# hero_board.net
KiCad netlist of a schematic drawn in EAGLE
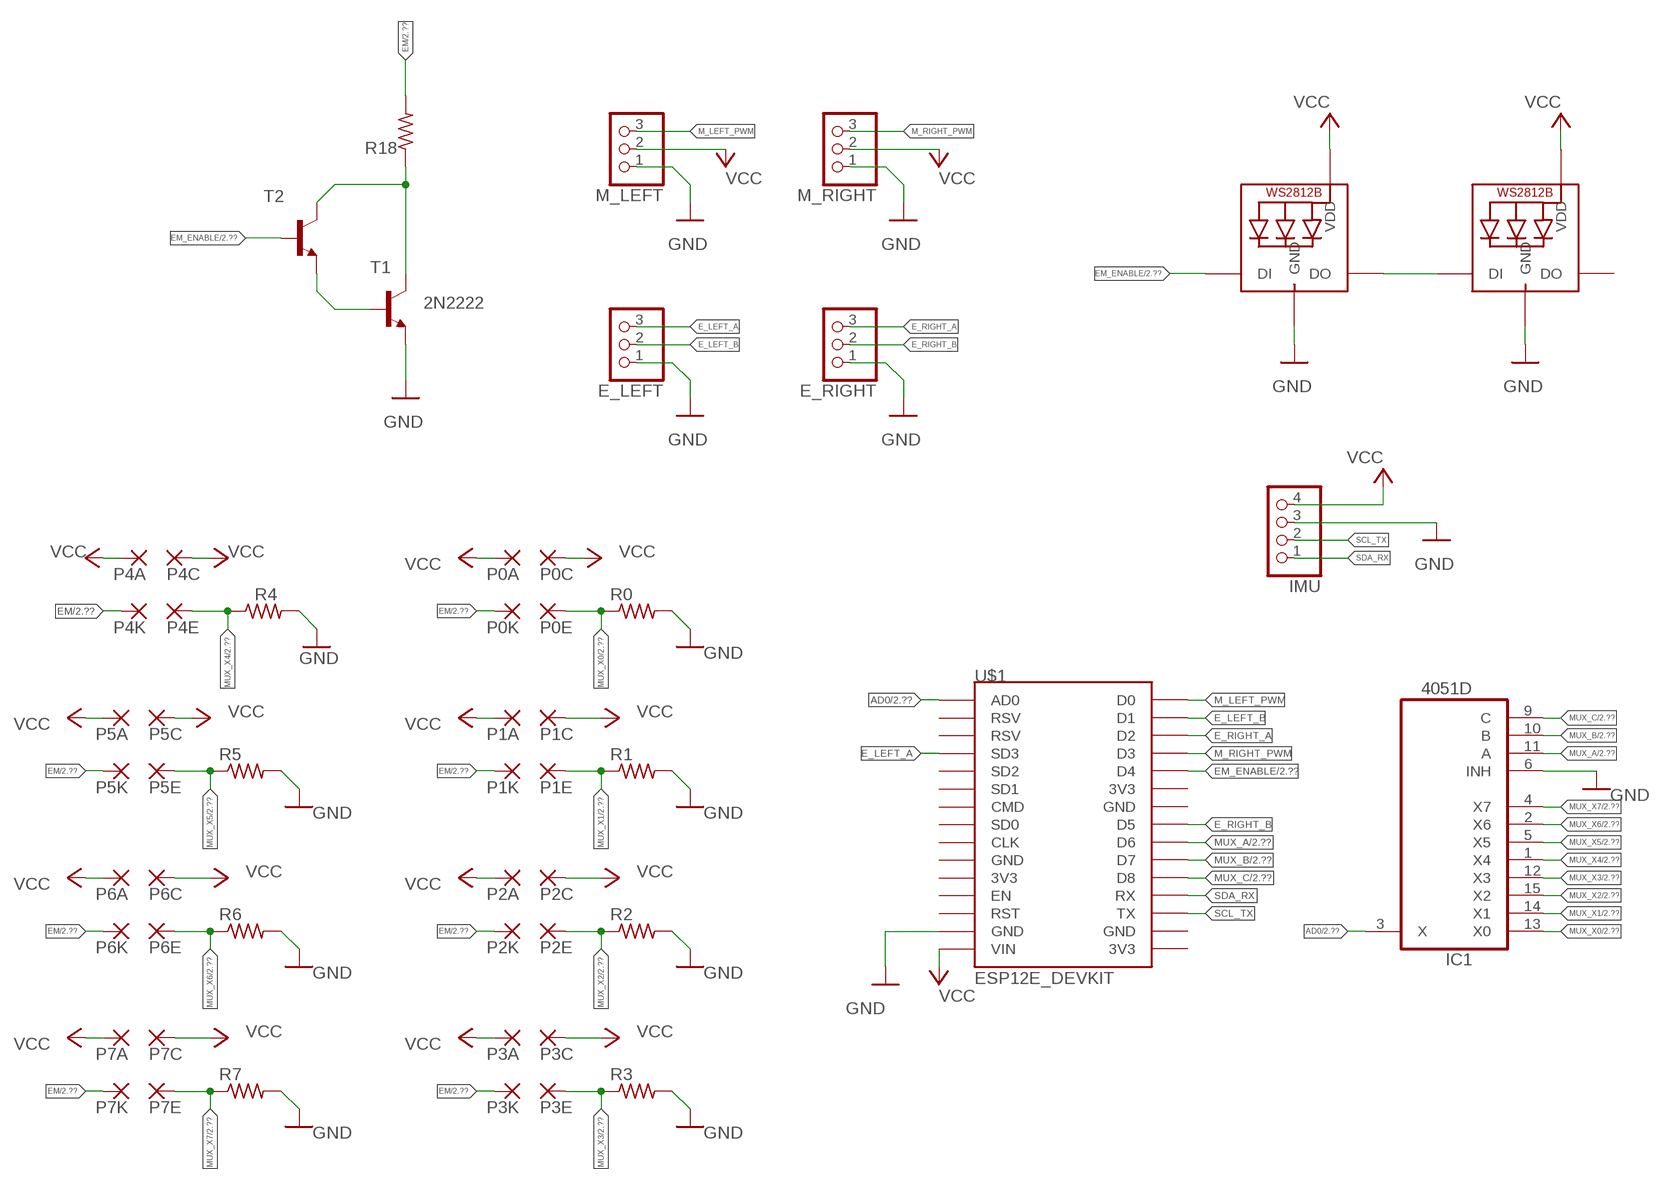
[diagram p0: schematic, sheet 1]
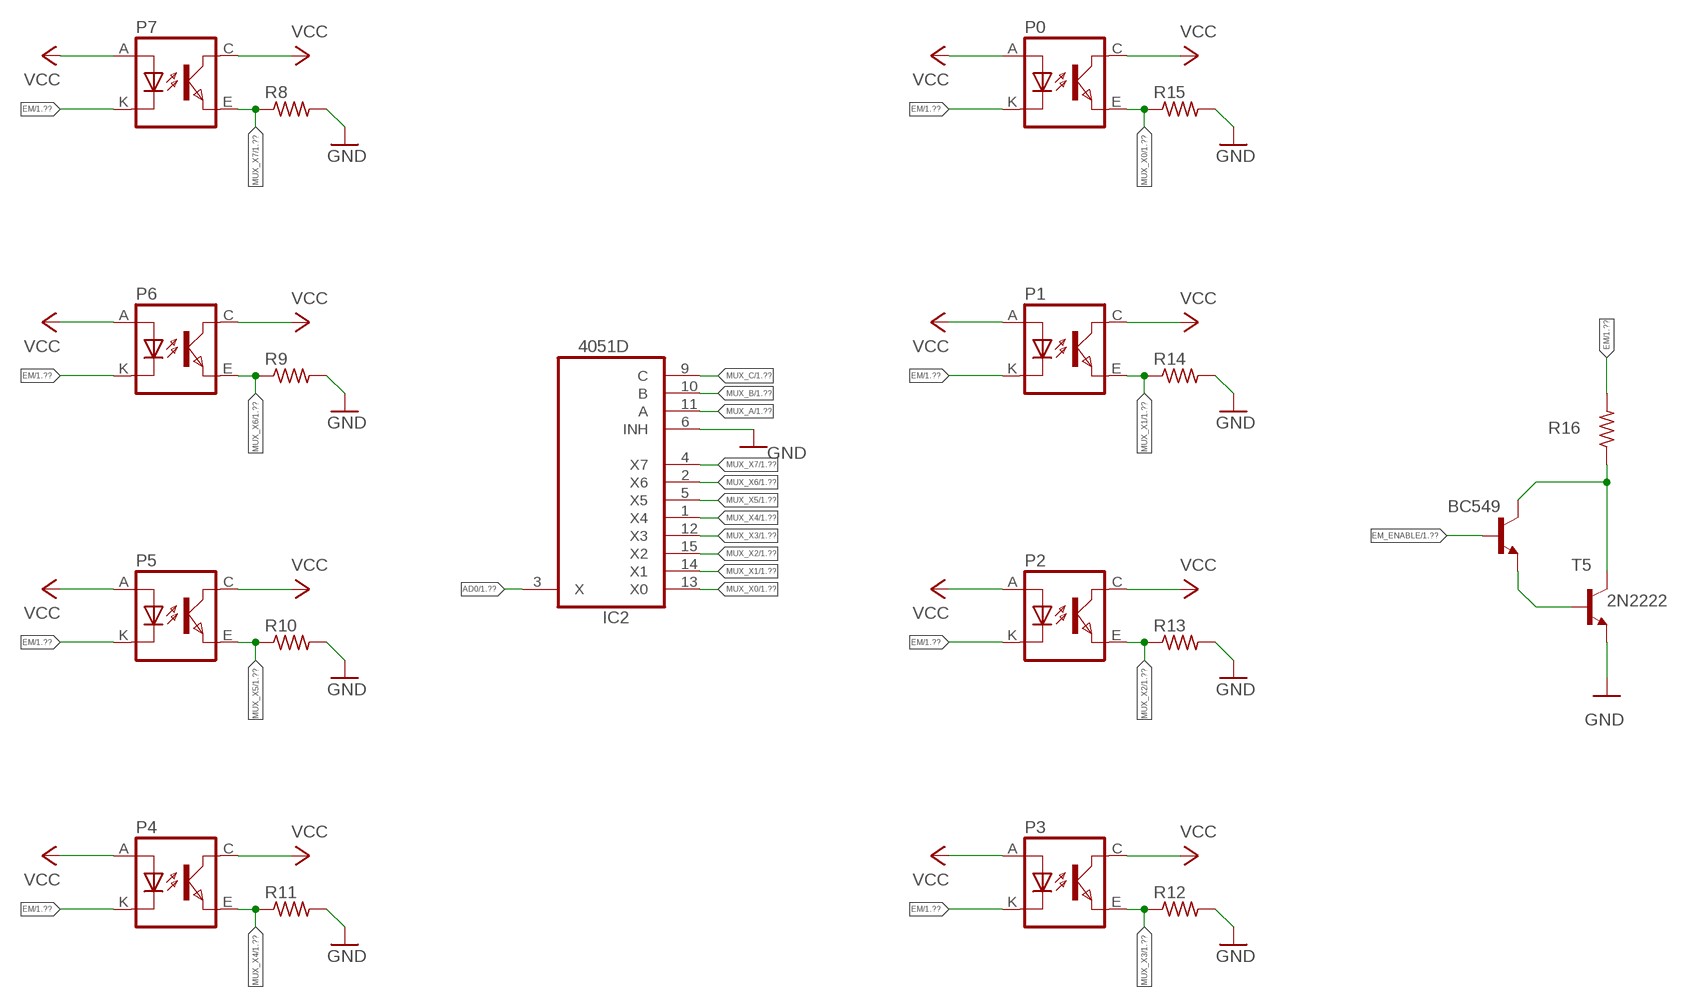
[diagram p1: schematic, sheet 2]

(export (version "E")
  (design (tool "Eeschema 10.0.6"))
  (components
    (comp (ref "BC549")
      (value "BC549-NPN-TO92-CBE")
      (footprint "eagle-import:TO92-CBE")
      (fields (field (name "SPICEPREFIX") "J"))
      (libsource (lib "eagle-import") (part "-NPN-TO92-CBEBC549"))
    )
    (comp (ref "IC2")
      (value "4051D")
      (footprint "eagle-import:SO16")
      (libsource (lib "eagle-import") (part "4051D"))
    )
    (comp (ref "P0")
      (value "TCRT5000")
      (footprint "eagle-import:TCRT5000")
      (libsource (lib "eagle-import") (part "TCRT5000"))
    )
    (comp (ref "P1")
      (value "TCRT5000")
      (footprint "eagle-import:TCRT5000")
      (libsource (lib "eagle-import") (part "TCRT5000"))
    )
    (comp (ref "P2")
      (value "TCRT5000")
      (footprint "eagle-import:TCRT5000")
      (libsource (lib "eagle-import") (part "TCRT5000"))
    )
    (comp (ref "P3")
      (value "TCRT5000")
      (footprint "eagle-import:TCRT5000")
      (libsource (lib "eagle-import") (part "TCRT5000"))
    )
    (comp (ref "P4")
      (value "TCRT5000")
      (footprint "eagle-import:TCRT5000")
      (libsource (lib "eagle-import") (part "TCRT5000"))
    )
    (comp (ref "P5")
      (value "TCRT5000")
      (footprint "eagle-import:TCRT5000")
      (libsource (lib "eagle-import") (part "TCRT5000"))
    )
    (comp (ref "P6")
      (value "TCRT5000")
      (footprint "eagle-import:TCRT5000")
      (libsource (lib "eagle-import") (part "TCRT5000"))
    )
    (comp (ref "P7")
      (value "TCRT5000")
      (footprint "eagle-import:TCRT5000")
      (libsource (lib "eagle-import") (part "TCRT5000"))
    )
    (comp (ref "R8")
      (value "R-US_M0805")
      (footprint "eagle-import:M0805")
      (libsource (lib "eagle-import") (part "R-US_M0805"))
    )
    (comp (ref "R9")
      (value "R-US_M0805")
      (footprint "eagle-import:M0805")
      (libsource (lib "eagle-import") (part "R-US_M0805"))
    )
    (comp (ref "R10")
      (value "R-US_M0805")
      (footprint "eagle-import:M0805")
      (libsource (lib "eagle-import") (part "R-US_M0805"))
    )
    (comp (ref "R11")
      (value "R-US_M0805")
      (footprint "eagle-import:M0805")
      (libsource (lib "eagle-import") (part "R-US_M0805"))
    )
    (comp (ref "R12")
      (value "R-US_M0805")
      (footprint "eagle-import:M0805")
      (libsource (lib "eagle-import") (part "R-US_M0805"))
    )
    (comp (ref "R13")
      (value "R-US_M0805")
      (footprint "eagle-import:M0805")
      (libsource (lib "eagle-import") (part "R-US_M0805"))
    )
    (comp (ref "R14")
      (value "R-US_M0805")
      (footprint "eagle-import:M0805")
      (libsource (lib "eagle-import") (part "R-US_M0805"))
    )
    (comp (ref "R15")
      (value "R-US_M0805")
      (footprint "eagle-import:M0805")
      (libsource (lib "eagle-import") (part "R-US_M0805"))
    )
    (comp (ref "R16")
      (value "R-US_R0805")
      (footprint "eagle-import:R0805")
      (fields (field (name "SPICEPREFIX") "R"))
      (libsource (lib "eagle-import") (part "resistor_348_R-US_R0805"))
    )
    (comp (ref "T5")
      (value "2N2222")
      (footprint "eagle-import:TO18")
      (fields (field (name "SPICEPREFIX") "J"))
      (libsource (lib "eagle-import") (part "2N2222"))
    )
    (comp (ref "E_LEFT")
      (value "PINHD-1X3")
      (footprint "eagle-import:1X03")
      (libsource (lib "eagle-import") (part "PINHD-1X3"))
    )
    (comp (ref "E_RIGHT")
      (value "PINHD-1X3")
      (footprint "eagle-import:1X03")
      (libsource (lib "eagle-import") (part "PINHD-1X3"))
    )
    (comp (ref "IC1")
      (value "4051D")
      (footprint "eagle-import:SO16")
      (libsource (lib "eagle-import") (part "4051D"))
    )
    (comp (ref "IMU")
      (value "PINHD-1X4")
      (footprint "eagle-import:1X04")
      (libsource (lib "eagle-import") (part "PINHD-1X4"))
    )
    (comp (ref "LED1")
      (value "WS2812B5050")
      (footprint "eagle-import:WS2812B")
      (libsource (lib "eagle-import") (part "WS2812B5050"))
    )
    (comp (ref "LED2")
      (value "WS2812B5050")
      (footprint "eagle-import:WS2812B")
      (libsource (lib "eagle-import") (part "WS2812B5050"))
    )
    (comp (ref "M_LEFT")
      (value "PINHD-1X3")
      (footprint "eagle-import:1X03")
      (libsource (lib "eagle-import") (part "PINHD-1X3"))
    )
    (comp (ref "M_RIGHT")
      (value "PINHD-1X3")
      (footprint "eagle-import:1X03")
      (libsource (lib "eagle-import") (part "PINHD-1X3"))
    )
    (comp (ref "P0A")
      (value "WIREPADSMD1,27-254")
      (footprint "eagle-import:SMD1,27-2,54")
      (libsource (lib "eagle-import") (part "WIREPADSMD1,27-254"))
    )
    (comp (ref "P0C")
      (value "WIREPADSMD1,27-254")
      (footprint "eagle-import:SMD1,27-2,54")
      (libsource (lib "eagle-import") (part "WIREPADSMD1,27-254"))
    )
    (comp (ref "P0E")
      (value "WIREPADSMD1,27-254")
      (footprint "eagle-import:SMD1,27-2,54")
      (libsource (lib "eagle-import") (part "WIREPADSMD1,27-254"))
    )
    (comp (ref "P0K")
      (value "WIREPADSMD1,27-254")
      (footprint "eagle-import:SMD1,27-2,54")
      (libsource (lib "eagle-import") (part "WIREPADSMD1,27-254"))
    )
    (comp (ref "P1A")
      (value "WIREPADSMD1,27-254")
      (footprint "eagle-import:SMD1,27-2,54")
      (libsource (lib "eagle-import") (part "WIREPADSMD1,27-254"))
    )
    (comp (ref "P1C")
      (value "WIREPADSMD1,27-254")
      (footprint "eagle-import:SMD1,27-2,54")
      (libsource (lib "eagle-import") (part "WIREPADSMD1,27-254"))
    )
    (comp (ref "P1E")
      (value "WIREPADSMD1,27-254")
      (footprint "eagle-import:SMD1,27-2,54")
      (libsource (lib "eagle-import") (part "WIREPADSMD1,27-254"))
    )
    (comp (ref "P1K")
      (value "WIREPADSMD1,27-254")
      (footprint "eagle-import:SMD1,27-2,54")
      (libsource (lib "eagle-import") (part "WIREPADSMD1,27-254"))
    )
    (comp (ref "P2A")
      (value "WIREPADSMD1,27-254")
      (footprint "eagle-import:SMD1,27-2,54")
      (libsource (lib "eagle-import") (part "WIREPADSMD1,27-254"))
    )
    (comp (ref "P2C")
      (value "WIREPADSMD1,27-254")
      (footprint "eagle-import:SMD1,27-2,54")
      (libsource (lib "eagle-import") (part "WIREPADSMD1,27-254"))
    )
    (comp (ref "P2E")
      (value "WIREPADSMD1,27-254")
      (footprint "eagle-import:SMD1,27-2,54")
      (libsource (lib "eagle-import") (part "WIREPADSMD1,27-254"))
    )
    (comp (ref "P2K")
      (value "WIREPADSMD1,27-254")
      (footprint "eagle-import:SMD1,27-2,54")
      (libsource (lib "eagle-import") (part "WIREPADSMD1,27-254"))
    )
    (comp (ref "P3A")
      (value "WIREPADSMD1,27-254")
      (footprint "eagle-import:SMD1,27-2,54")
      (libsource (lib "eagle-import") (part "WIREPADSMD1,27-254"))
    )
    (comp (ref "P3C")
      (value "WIREPADSMD1,27-254")
      (footprint "eagle-import:SMD1,27-2,54")
      (libsource (lib "eagle-import") (part "WIREPADSMD1,27-254"))
    )
    (comp (ref "P3E")
      (value "WIREPADSMD1,27-254")
      (footprint "eagle-import:SMD1,27-2,54")
      (libsource (lib "eagle-import") (part "WIREPADSMD1,27-254"))
    )
    (comp (ref "P3K")
      (value "WIREPADSMD1,27-254")
      (footprint "eagle-import:SMD1,27-2,54")
      (libsource (lib "eagle-import") (part "WIREPADSMD1,27-254"))
    )
    (comp (ref "P4A")
      (value "WIREPADSMD1,27-254")
      (footprint "eagle-import:SMD1,27-2,54")
      (libsource (lib "eagle-import") (part "WIREPADSMD1,27-254"))
    )
    (comp (ref "P4C")
      (value "WIREPADSMD1,27-254")
      (footprint "eagle-import:SMD1,27-2,54")
      (libsource (lib "eagle-import") (part "WIREPADSMD1,27-254"))
    )
    (comp (ref "P4E")
      (value "WIREPADSMD1,27-254")
      (footprint "eagle-import:SMD1,27-2,54")
      (libsource (lib "eagle-import") (part "WIREPADSMD1,27-254"))
    )
    (comp (ref "P4K")
      (value "WIREPADSMD1,27-254")
      (footprint "eagle-import:SMD1,27-2,54")
      (libsource (lib "eagle-import") (part "WIREPADSMD1,27-254"))
    )
    (comp (ref "P5A")
      (value "WIREPADSMD1,27-254")
      (footprint "eagle-import:SMD1,27-2,54")
      (libsource (lib "eagle-import") (part "WIREPADSMD1,27-254"))
    )
    (comp (ref "P5C")
      (value "WIREPADSMD1,27-254")
      (footprint "eagle-import:SMD1,27-2,54")
      (libsource (lib "eagle-import") (part "WIREPADSMD1,27-254"))
    )
    (comp (ref "P5E")
      (value "WIREPADSMD1,27-254")
      (footprint "eagle-import:SMD1,27-2,54")
      (libsource (lib "eagle-import") (part "WIREPADSMD1,27-254"))
    )
    (comp (ref "P5K")
      (value "WIREPADSMD1,27-254")
      (footprint "eagle-import:SMD1,27-2,54")
      (libsource (lib "eagle-import") (part "WIREPADSMD1,27-254"))
    )
    (comp (ref "P6A")
      (value "WIREPADSMD1,27-254")
      (footprint "eagle-import:SMD1,27-2,54")
      (libsource (lib "eagle-import") (part "WIREPADSMD1,27-254"))
    )
    (comp (ref "P6C")
      (value "WIREPADSMD1,27-254")
      (footprint "eagle-import:SMD1,27-2,54")
      (libsource (lib "eagle-import") (part "WIREPADSMD1,27-254"))
    )
    (comp (ref "P6E")
      (value "WIREPADSMD1,27-254")
      (footprint "eagle-import:SMD1,27-2,54")
      (libsource (lib "eagle-import") (part "WIREPADSMD1,27-254"))
    )
    (comp (ref "P6K")
      (value "WIREPADSMD1,27-254")
      (footprint "eagle-import:SMD1,27-2,54")
      (libsource (lib "eagle-import") (part "WIREPADSMD1,27-254"))
    )
    (comp (ref "P7A")
      (value "WIREPADSMD1,27-254")
      (footprint "eagle-import:SMD1,27-2,54")
      (libsource (lib "eagle-import") (part "WIREPADSMD1,27-254"))
    )
    (comp (ref "P7C")
      (value "WIREPADSMD1,27-254")
      (footprint "eagle-import:SMD1,27-2,54")
      (libsource (lib "eagle-import") (part "WIREPADSMD1,27-254"))
    )
    (comp (ref "P7E")
      (value "WIREPADSMD1,27-254")
      (footprint "eagle-import:SMD1,27-2,54")
      (libsource (lib "eagle-import") (part "WIREPADSMD1,27-254"))
    )
    (comp (ref "P7K")
      (value "WIREPADSMD1,27-254")
      (footprint "eagle-import:SMD1,27-2,54")
      (libsource (lib "eagle-import") (part "WIREPADSMD1,27-254"))
    )
    (comp (ref "R0")
      (value "R-US_R0805")
      (footprint "eagle-import:R0805")
      (libsource (lib "eagle-import") (part "resistor_348_R-US_R0805"))
    )
    (comp (ref "R1")
      (value "R-US_R0805")
      (footprint "eagle-import:R0805")
      (libsource (lib "eagle-import") (part "resistor_348_R-US_R0805"))
    )
    (comp (ref "R2")
      (value "R-US_R0805")
      (footprint "eagle-import:R0805")
      (libsource (lib "eagle-import") (part "resistor_348_R-US_R0805"))
    )
    (comp (ref "R3")
      (value "R-US_R0805")
      (footprint "eagle-import:R0805")
      (libsource (lib "eagle-import") (part "resistor_348_R-US_R0805"))
    )
    (comp (ref "R4")
      (value "R-US_R0805")
      (footprint "eagle-import:R0805")
      (libsource (lib "eagle-import") (part "resistor_348_R-US_R0805"))
    )
    (comp (ref "R5")
      (value "R-US_R0805")
      (footprint "eagle-import:R0805")
      (libsource (lib "eagle-import") (part "resistor_348_R-US_R0805"))
    )
    (comp (ref "R6")
      (value "R-US_R0805")
      (footprint "eagle-import:R0805")
      (libsource (lib "eagle-import") (part "resistor_348_R-US_R0805"))
    )
    (comp (ref "R7")
      (value "R-US_R0805")
      (footprint "eagle-import:R0805")
      (libsource (lib "eagle-import") (part "resistor_348_R-US_R0805"))
    )
    (comp (ref "R18")
      (value "R-US_R0805")
      (footprint "eagle-import:R0805")
      (libsource (lib "eagle-import") (part "resistor_348_R-US_R0805"))
    )
    (comp (ref "T1")
      (value "2N2222")
      (footprint "eagle-import:TO18")
      (libsource (lib "eagle-import") (part "2N2222"))
    )
    (comp (ref "T2")
      (value "BC549-NPN-TO92-CBE")
      (footprint "eagle-import:TO92-CBE")
      (libsource (lib "eagle-import") (part "-NPN-TO92-CBEBC549"))
    )
    (comp (ref "U$1")
      (value "ESP12E_DEVKIT")
      (footprint "eagle-import:ESP12E_DEVKIT")
      (libsource (lib "eagle-import") (part "ESP12E_DEVKIT"))
    )
  )
  (nets
    (net (code "1") (name "AD0") (class "Default")
      (node (ref "IC1") (pin "3") (pinfunction "X_3") (pintype "bidirectional"))
      (node (ref "IC2") (pin "3") (pinfunction "X_3") (pintype "bidirectional"))
      (node (ref "U$1") (pin "AD0") (pinfunction "AD0_AD0") (pintype "bidirectional"))
    )
    (net (code "2") (name "EM") (class "Default")
      (node (ref "P0") (pin "K") (pinfunction "CATHODE_K") (pintype "passive"))
      (node (ref "P0K") (pin "1") (pinfunction "P_1") (pintype "passive"))
      (node (ref "P1") (pin "K") (pinfunction "CATHODE_K") (pintype "passive"))
      (node (ref "P1K") (pin "1") (pinfunction "P_1") (pintype "passive"))
      (node (ref "P2") (pin "K") (pinfunction "CATHODE_K") (pintype "passive"))
      (node (ref "P2K") (pin "1") (pinfunction "P_1") (pintype "passive"))
      (node (ref "P3") (pin "K") (pinfunction "CATHODE_K") (pintype "passive"))
      (node (ref "P3K") (pin "1") (pinfunction "P_1") (pintype "passive"))
      (node (ref "P4") (pin "K") (pinfunction "CATHODE_K") (pintype "passive"))
      (node (ref "P4K") (pin "1") (pinfunction "P_1") (pintype "passive"))
      (node (ref "P5") (pin "K") (pinfunction "CATHODE_K") (pintype "passive"))
      (node (ref "P5K") (pin "1") (pinfunction "P_1") (pintype "passive"))
      (node (ref "P6") (pin "K") (pinfunction "CATHODE_K") (pintype "passive"))
      (node (ref "P6K") (pin "1") (pinfunction "P_1") (pintype "passive"))
      (node (ref "P7") (pin "K") (pinfunction "CATHODE_K") (pintype "passive"))
      (node (ref "P7K") (pin "1") (pinfunction "P_1") (pintype "passive"))
      (node (ref "R16") (pin "2") (pinfunction "2_2") (pintype "passive"))
      (node (ref "R18") (pin "2") (pinfunction "2_2") (pintype "passive"))
    )
    (net (code "3") (name "EM_ENABLE") (class "Default")
      (node (ref "BC549") (pin "B") (pinfunction "B_B") (pintype "passive"))
      (node (ref "LED1") (pin "4-DIN") (pinfunction "DI_4-DIN") (pintype "input"))
      (node (ref "T2") (pin "B") (pinfunction "B_B") (pintype "passive"))
      (node (ref "U$1") (pin "D4") (pinfunction "D4_D4") (pintype "bidirectional"))
    )
    (net (code "4") (name "E_LEFT_A") (class "Default")
      (node (ref "E_LEFT") (pin "3") (pinfunction "3_3") (pintype "passive"))
      (node (ref "U$1") (pin "SD3") (pinfunction "SD3_SD3") (pintype "bidirectional"))
    )
    (net (code "5") (name "E_LEFT_B") (class "Default")
      (node (ref "E_LEFT") (pin "2") (pinfunction "2_2") (pintype "passive"))
      (node (ref "U$1") (pin "D1") (pinfunction "D1_D1") (pintype "bidirectional"))
    )
    (net (code "6") (name "E_RIGHT_A") (class "Default")
      (node (ref "E_RIGHT") (pin "3") (pinfunction "3_3") (pintype "passive"))
      (node (ref "U$1") (pin "D2") (pinfunction "D2_D2") (pintype "bidirectional"))
    )
    (net (code "7") (name "E_RIGHT_B") (class "Default")
      (node (ref "E_RIGHT") (pin "2") (pinfunction "2_2") (pintype "passive"))
      (node (ref "U$1") (pin "D5") (pinfunction "D5_D5") (pintype "bidirectional"))
    )
    (net (code "8") (name "GND") (class "Default")
      (node (ref "E_LEFT") (pin "1") (pinfunction "1_1") (pintype "passive"))
      (node (ref "E_RIGHT") (pin "1") (pinfunction "1_1") (pintype "passive"))
      (node (ref "IC1") (pin "6") (pinfunction "INH_6") (pintype "input"))
      (node (ref "IC2") (pin "6") (pinfunction "INH_6") (pintype "input"))
      (node (ref "IMU") (pin "3") (pinfunction "3_3") (pintype "passive"))
      (node (ref "LED1") (pin "3-GND") (pinfunction "GND_3-GND") (pintype "power_in"))
      (node (ref "LED2") (pin "3-GND") (pinfunction "GND_3-GND") (pintype "power_in"))
      (node (ref "M_LEFT") (pin "1") (pinfunction "1_1") (pintype "passive"))
      (node (ref "M_RIGHT") (pin "1") (pinfunction "1_1") (pintype "passive"))
      (node (ref "R0") (pin "2") (pinfunction "2_2") (pintype "passive"))
      (node (ref "R1") (pin "2") (pinfunction "2_2") (pintype "passive"))
      (node (ref "R10") (pin "2") (pinfunction "2_2") (pintype "passive"))
      (node (ref "R11") (pin "2") (pinfunction "2_2") (pintype "passive"))
      (node (ref "R12") (pin "2") (pinfunction "2_2") (pintype "passive"))
      (node (ref "R13") (pin "2") (pinfunction "2_2") (pintype "passive"))
      (node (ref "R14") (pin "2") (pinfunction "2_2") (pintype "passive"))
      (node (ref "R15") (pin "2") (pinfunction "2_2") (pintype "passive"))
      (node (ref "R2") (pin "2") (pinfunction "2_2") (pintype "passive"))
      (node (ref "R3") (pin "2") (pinfunction "2_2") (pintype "passive"))
      (node (ref "R4") (pin "2") (pinfunction "2_2") (pintype "passive"))
      (node (ref "R5") (pin "2") (pinfunction "2_2") (pintype "passive"))
      (node (ref "R6") (pin "2") (pinfunction "2_2") (pintype "passive"))
      (node (ref "R7") (pin "2") (pinfunction "2_2") (pintype "passive"))
      (node (ref "R8") (pin "2") (pinfunction "2_2") (pintype "passive"))
      (node (ref "R9") (pin "2") (pinfunction "2_2") (pintype "passive"))
      (node (ref "T1") (pin "1") (pinfunction "E_1") (pintype "passive"))
      (node (ref "T5") (pin "1") (pinfunction "E_1") (pintype "passive"))
      (node (ref "U$1") (pin "GND@1") (pinfunction "GND_GND@1") (pintype "bidirectional"))
    )
    (net (code "9") (name "MUX_A") (class "Default")
      (node (ref "IC1") (pin "11") (pinfunction "A_11") (pintype "input"))
      (node (ref "IC2") (pin "11") (pinfunction "A_11") (pintype "input"))
      (node (ref "U$1") (pin "D6") (pinfunction "D6_D6") (pintype "bidirectional"))
    )
    (net (code "10") (name "MUX_B") (class "Default")
      (node (ref "IC1") (pin "10") (pinfunction "B_10") (pintype "input"))
      (node (ref "IC2") (pin "10") (pinfunction "B_10") (pintype "input"))
      (node (ref "U$1") (pin "D7") (pinfunction "D7_D7") (pintype "bidirectional"))
    )
    (net (code "11") (name "MUX_C") (class "Default")
      (node (ref "IC1") (pin "9") (pinfunction "C_9") (pintype "input"))
      (node (ref "IC2") (pin "9") (pinfunction "C_9") (pintype "input"))
      (node (ref "U$1") (pin "D8") (pinfunction "D8_D8") (pintype "bidirectional"))
    )
    (net (code "12") (name "MUX_X0") (class "Default")
      (node (ref "IC1") (pin "13") (pinfunction "X0_13") (pintype "bidirectional"))
      (node (ref "IC2") (pin "13") (pinfunction "X0_13") (pintype "bidirectional"))
      (node (ref "P0") (pin "E") (pinfunction "EMITTER_E") (pintype "passive"))
      (node (ref "P0E") (pin "1") (pinfunction "P_1") (pintype "passive"))
      (node (ref "R0") (pin "1") (pinfunction "1_1") (pintype "passive"))
      (node (ref "R15") (pin "1") (pinfunction "1_1") (pintype "passive"))
    )
    (net (code "13") (name "MUX_X1") (class "Default")
      (node (ref "IC1") (pin "14") (pinfunction "X1_14") (pintype "bidirectional"))
      (node (ref "IC2") (pin "14") (pinfunction "X1_14") (pintype "bidirectional"))
      (node (ref "P1") (pin "E") (pinfunction "EMITTER_E") (pintype "passive"))
      (node (ref "P1E") (pin "1") (pinfunction "P_1") (pintype "passive"))
      (node (ref "R1") (pin "1") (pinfunction "1_1") (pintype "passive"))
      (node (ref "R14") (pin "1") (pinfunction "1_1") (pintype "passive"))
    )
    (net (code "14") (name "MUX_X2") (class "Default")
      (node (ref "IC1") (pin "15") (pinfunction "X2_15") (pintype "bidirectional"))
      (node (ref "IC2") (pin "15") (pinfunction "X2_15") (pintype "bidirectional"))
      (node (ref "P2") (pin "E") (pinfunction "EMITTER_E") (pintype "passive"))
      (node (ref "P2E") (pin "1") (pinfunction "P_1") (pintype "passive"))
      (node (ref "R13") (pin "1") (pinfunction "1_1") (pintype "passive"))
      (node (ref "R2") (pin "1") (pinfunction "1_1") (pintype "passive"))
    )
    (net (code "15") (name "MUX_X3") (class "Default")
      (node (ref "IC1") (pin "12") (pinfunction "X3_12") (pintype "bidirectional"))
      (node (ref "IC2") (pin "12") (pinfunction "X3_12") (pintype "bidirectional"))
      (node (ref "P3") (pin "E") (pinfunction "EMITTER_E") (pintype "passive"))
      (node (ref "P3E") (pin "1") (pinfunction "P_1") (pintype "passive"))
      (node (ref "R12") (pin "1") (pinfunction "1_1") (pintype "passive"))
      (node (ref "R3") (pin "1") (pinfunction "1_1") (pintype "passive"))
    )
    (net (code "16") (name "MUX_X4") (class "Default")
      (node (ref "IC1") (pin "1") (pinfunction "X4_1") (pintype "bidirectional"))
      (node (ref "IC2") (pin "1") (pinfunction "X4_1") (pintype "bidirectional"))
      (node (ref "P4") (pin "E") (pinfunction "EMITTER_E") (pintype "passive"))
      (node (ref "P4E") (pin "1") (pinfunction "P_1") (pintype "passive"))
      (node (ref "R11") (pin "1") (pinfunction "1_1") (pintype "passive"))
      (node (ref "R4") (pin "1") (pinfunction "1_1") (pintype "passive"))
    )
    (net (code "17") (name "MUX_X5") (class "Default")
      (node (ref "IC1") (pin "5") (pinfunction "X5_5") (pintype "bidirectional"))
      (node (ref "IC2") (pin "5") (pinfunction "X5_5") (pintype "bidirectional"))
      (node (ref "P5") (pin "E") (pinfunction "EMITTER_E") (pintype "passive"))
      (node (ref "P5E") (pin "1") (pinfunction "P_1") (pintype "passive"))
      (node (ref "R10") (pin "1") (pinfunction "1_1") (pintype "passive"))
      (node (ref "R5") (pin "1") (pinfunction "1_1") (pintype "passive"))
    )
    (net (code "18") (name "MUX_X6") (class "Default")
      (node (ref "IC1") (pin "2") (pinfunction "X6_2") (pintype "bidirectional"))
      (node (ref "IC2") (pin "2") (pinfunction "X6_2") (pintype "bidirectional"))
      (node (ref "P6") (pin "E") (pinfunction "EMITTER_E") (pintype "passive"))
      (node (ref "P6E") (pin "1") (pinfunction "P_1") (pintype "passive"))
      (node (ref "R6") (pin "1") (pinfunction "1_1") (pintype "passive"))
      (node (ref "R9") (pin "1") (pinfunction "1_1") (pintype "passive"))
    )
    (net (code "19") (name "MUX_X7") (class "Default")
      (node (ref "IC1") (pin "4") (pinfunction "X7_4") (pintype "bidirectional"))
      (node (ref "IC2") (pin "4") (pinfunction "X7_4") (pintype "bidirectional"))
      (node (ref "P7") (pin "E") (pinfunction "EMITTER_E") (pintype "passive"))
      (node (ref "P7E") (pin "1") (pinfunction "P_1") (pintype "passive"))
      (node (ref "R7") (pin "1") (pinfunction "1_1") (pintype "passive"))
      (node (ref "R8") (pin "1") (pinfunction "1_1") (pintype "passive"))
    )
    (net (code "20") (name "M_LEFT_PWM") (class "Default")
      (node (ref "M_LEFT") (pin "3") (pinfunction "3_3") (pintype "passive"))
      (node (ref "U$1") (pin "D0") (pinfunction "D0_D0") (pintype "bidirectional"))
    )
    (net (code "21") (name "M_RIGHT_PWM") (class "Default")
      (node (ref "M_RIGHT") (pin "3") (pinfunction "3_3") (pintype "passive"))
      (node (ref "U$1") (pin "D3") (pinfunction "D3_D3") (pintype "bidirectional"))
    )
    (net (code "22") (name "Net-(LED1-DO)") (class "Default")
      (node (ref "LED1") (pin "2-DOUT") (pinfunction "DO_2-DOUT") (pintype "output"))
      (node (ref "LED2") (pin "4-DIN") (pinfunction "DI_4-DIN") (pintype "input"))
    )
    (net (code "23") (name "Net-(T1-B)") (class "Default")
      (node (ref "T1") (pin "2") (pinfunction "B_2") (pintype "passive"))
      (node (ref "T2") (pin "E") (pinfunction "E_E") (pintype "passive"))
    )
    (net (code "24") (name "Net-(T1-C)") (class "Default")
      (node (ref "R18") (pin "1") (pinfunction "1_1") (pintype "passive"))
      (node (ref "T1") (pin "3") (pinfunction "C_3") (pintype "passive"))
      (node (ref "T2") (pin "C") (pinfunction "C_C") (pintype "passive"))
    )
    (net (code "25") (name "Net-(T5-B)") (class "Default")
      (node (ref "BC549") (pin "E") (pinfunction "E_E") (pintype "passive"))
      (node (ref "T5") (pin "2") (pinfunction "B_2") (pintype "passive"))
    )
    (net (code "26") (name "Net-(T5-C)") (class "Default")
      (node (ref "BC549") (pin "C") (pinfunction "C_C") (pintype "passive"))
      (node (ref "R16") (pin "1") (pinfunction "1_1") (pintype "passive"))
      (node (ref "T5") (pin "3") (pinfunction "C_3") (pintype "passive"))
    )
    (net (code "27") (name "SCL_TX") (class "Default")
      (node (ref "IMU") (pin "2") (pinfunction "2_2") (pintype "passive"))
      (node (ref "U$1") (pin "TX") (pinfunction "TX_TX") (pintype "bidirectional"))
    )
    (net (code "28") (name "SDA_RX") (class "Default")
      (node (ref "IMU") (pin "1") (pinfunction "1_1") (pintype "passive"))
      (node (ref "U$1") (pin "RX") (pinfunction "RX_RX") (pintype "bidirectional"))
    )
    (net (code "29") (name "VCC") (class "Default")
      (node (ref "IMU") (pin "4") (pinfunction "4_4") (pintype "passive"))
      (node (ref "LED1") (pin "1-VDD") (pinfunction "VDD_1-VDD") (pintype "power_in"))
      (node (ref "LED2") (pin "1-VDD") (pinfunction "VDD_1-VDD") (pintype "power_in"))
      (node (ref "M_LEFT") (pin "2") (pinfunction "2_2") (pintype "passive"))
      (node (ref "M_RIGHT") (pin "2") (pinfunction "2_2") (pintype "passive"))
      (node (ref "P0") (pin "A") (pinfunction "ANODE_A") (pintype "passive"))
      (node (ref "P0") (pin "C") (pinfunction "COLLECTOR_C") (pintype "passive"))
      (node (ref "P0A") (pin "1") (pinfunction "P_1") (pintype "passive"))
      (node (ref "P0C") (pin "1") (pinfunction "P_1") (pintype "passive"))
      (node (ref "P1") (pin "A") (pinfunction "ANODE_A") (pintype "passive"))
      (node (ref "P1") (pin "C") (pinfunction "COLLECTOR_C") (pintype "passive"))
      (node (ref "P1A") (pin "1") (pinfunction "P_1") (pintype "passive"))
      (node (ref "P1C") (pin "1") (pinfunction "P_1") (pintype "passive"))
      (node (ref "P2") (pin "A") (pinfunction "ANODE_A") (pintype "passive"))
      (node (ref "P2") (pin "C") (pinfunction "COLLECTOR_C") (pintype "passive"))
      (node (ref "P2A") (pin "1") (pinfunction "P_1") (pintype "passive"))
      (node (ref "P2C") (pin "1") (pinfunction "P_1") (pintype "passive"))
      (node (ref "P3") (pin "A") (pinfunction "ANODE_A") (pintype "passive"))
      (node (ref "P3") (pin "C") (pinfunction "COLLECTOR_C") (pintype "passive"))
      (node (ref "P3A") (pin "1") (pinfunction "P_1") (pintype "passive"))
      (node (ref "P3C") (pin "1") (pinfunction "P_1") (pintype "passive"))
      (node (ref "P4") (pin "A") (pinfunction "ANODE_A") (pintype "passive"))
      (node (ref "P4") (pin "C") (pinfunction "COLLECTOR_C") (pintype "passive"))
      (node (ref "P4A") (pin "1") (pinfunction "P_1") (pintype "passive"))
      (node (ref "P4C") (pin "1") (pinfunction "P_1") (pintype "passive"))
      (node (ref "P5") (pin "A") (pinfunction "ANODE_A") (pintype "passive"))
      (node (ref "P5") (pin "C") (pinfunction "COLLECTOR_C") (pintype "passive"))
      (node (ref "P5A") (pin "1") (pinfunction "P_1") (pintype "passive"))
      (node (ref "P5C") (pin "1") (pinfunction "P_1") (pintype "passive"))
      (node (ref "P6") (pin "A") (pinfunction "ANODE_A") (pintype "passive"))
      (node (ref "P6") (pin "C") (pinfunction "COLLECTOR_C") (pintype "passive"))
      (node (ref "P6A") (pin "1") (pinfunction "P_1") (pintype "passive"))
      (node (ref "P6C") (pin "1") (pinfunction "P_1") (pintype "passive"))
      (node (ref "P7") (pin "A") (pinfunction "ANODE_A") (pintype "passive"))
      (node (ref "P7") (pin "C") (pinfunction "COLLECTOR_C") (pintype "passive"))
      (node (ref "P7A") (pin "1") (pinfunction "P_1") (pintype "passive"))
      (node (ref "P7C") (pin "1") (pinfunction "P_1") (pintype "passive"))
      (node (ref "U$1") (pin "VIN") (pinfunction "VIN_VIN") (pintype "bidirectional"))
    )
    (net (code "30") (name "unconnected-(LED2-DO-Pad2-DOUT)") (class "Default")
      (node (ref "LED2") (pin "2-DOUT") (pinfunction "DO_2-DOUT") (pintype "output"))
    )
    (net (code "31") (name "unconnected-(U$1-3V3-Pad3V3@0)") (class "Default")
      (node (ref "U$1") (pin "3V3@0") (pinfunction "3V3_3V3@0") (pintype "bidirectional"))
    )
    (net (code "32") (name "unconnected-(U$1-3V3-Pad3V3@1)") (class "Default")
      (node (ref "U$1") (pin "3V3@1") (pinfunction "3V3_3V3@1") (pintype "bidirectional"))
    )
    (net (code "33") (name "unconnected-(U$1-3V3-Pad3V3@2)") (class "Default")
      (node (ref "U$1") (pin "3V3@2") (pinfunction "3V3_3V3@2") (pintype "bidirectional"))
    )
    (net (code "34") (name "unconnected-(U$1-GND-PadGND@0)") (class "Default")
      (node (ref "U$1") (pin "GND@0") (pinfunction "GND_GND@0") (pintype "bidirectional"))
    )
    (net (code "35") (name "unconnected-(U$1-GND-PadGND@2)") (class "Default")
      (node (ref "U$1") (pin "GND@2") (pinfunction "GND_GND@2") (pintype "bidirectional"))
    )
    (net (code "36") (name "unconnected-(U$1-GND-PadGND@3)") (class "Default")
      (node (ref "U$1") (pin "GND@3") (pinfunction "GND_GND@3") (pintype "bidirectional"))
    )
    (net (code "37") (name "unconnected-(U$1-PadCLK)") (class "Default")
      (node (ref "U$1") (pin "CLK") (pinfunction "CLK_CLK") (pintype "bidirectional"))
    )
    (net (code "38") (name "unconnected-(U$1-PadCMD)") (class "Default")
      (node (ref "U$1") (pin "CMD") (pinfunction "CMD_CMD") (pintype "bidirectional"))
    )
    (net (code "39") (name "unconnected-(U$1-PadEN)") (class "Default")
      (node (ref "U$1") (pin "EN") (pinfunction "EN_EN") (pintype "bidirectional"))
    )
    (net (code "40") (name "unconnected-(U$1-PadRST)") (class "Default")
      (node (ref "U$1") (pin "RST") (pinfunction "RST_RST") (pintype "bidirectional"))
    )
    (net (code "41") (name "unconnected-(U$1-PadSD0)") (class "Default")
      (node (ref "U$1") (pin "SD0") (pinfunction "SD0_SD0") (pintype "bidirectional"))
    )
    (net (code "42") (name "unconnected-(U$1-PadSD1)") (class "Default")
      (node (ref "U$1") (pin "SD1") (pinfunction "SD1_SD1") (pintype "bidirectional"))
    )
    (net (code "43") (name "unconnected-(U$1-PadSD2)") (class "Default")
      (node (ref "U$1") (pin "SD2") (pinfunction "SD2_SD2") (pintype "bidirectional"))
    )
    (net (code "44") (name "unconnected-(U$1-RSV-PadRSV@0)") (class "Default")
      (node (ref "U$1") (pin "RSV@0") (pinfunction "RSV_RSV@0") (pintype "bidirectional"))
    )
    (net (code "45") (name "unconnected-(U$1-RSV-PadRSV@1)") (class "Default")
      (node (ref "U$1") (pin "RSV@1") (pinfunction "RSV_RSV@1") (pintype "bidirectional"))
    )
  )
)
